# SH05-DDS.net
KiCad netlist of a schematic drawn in Altium Designer
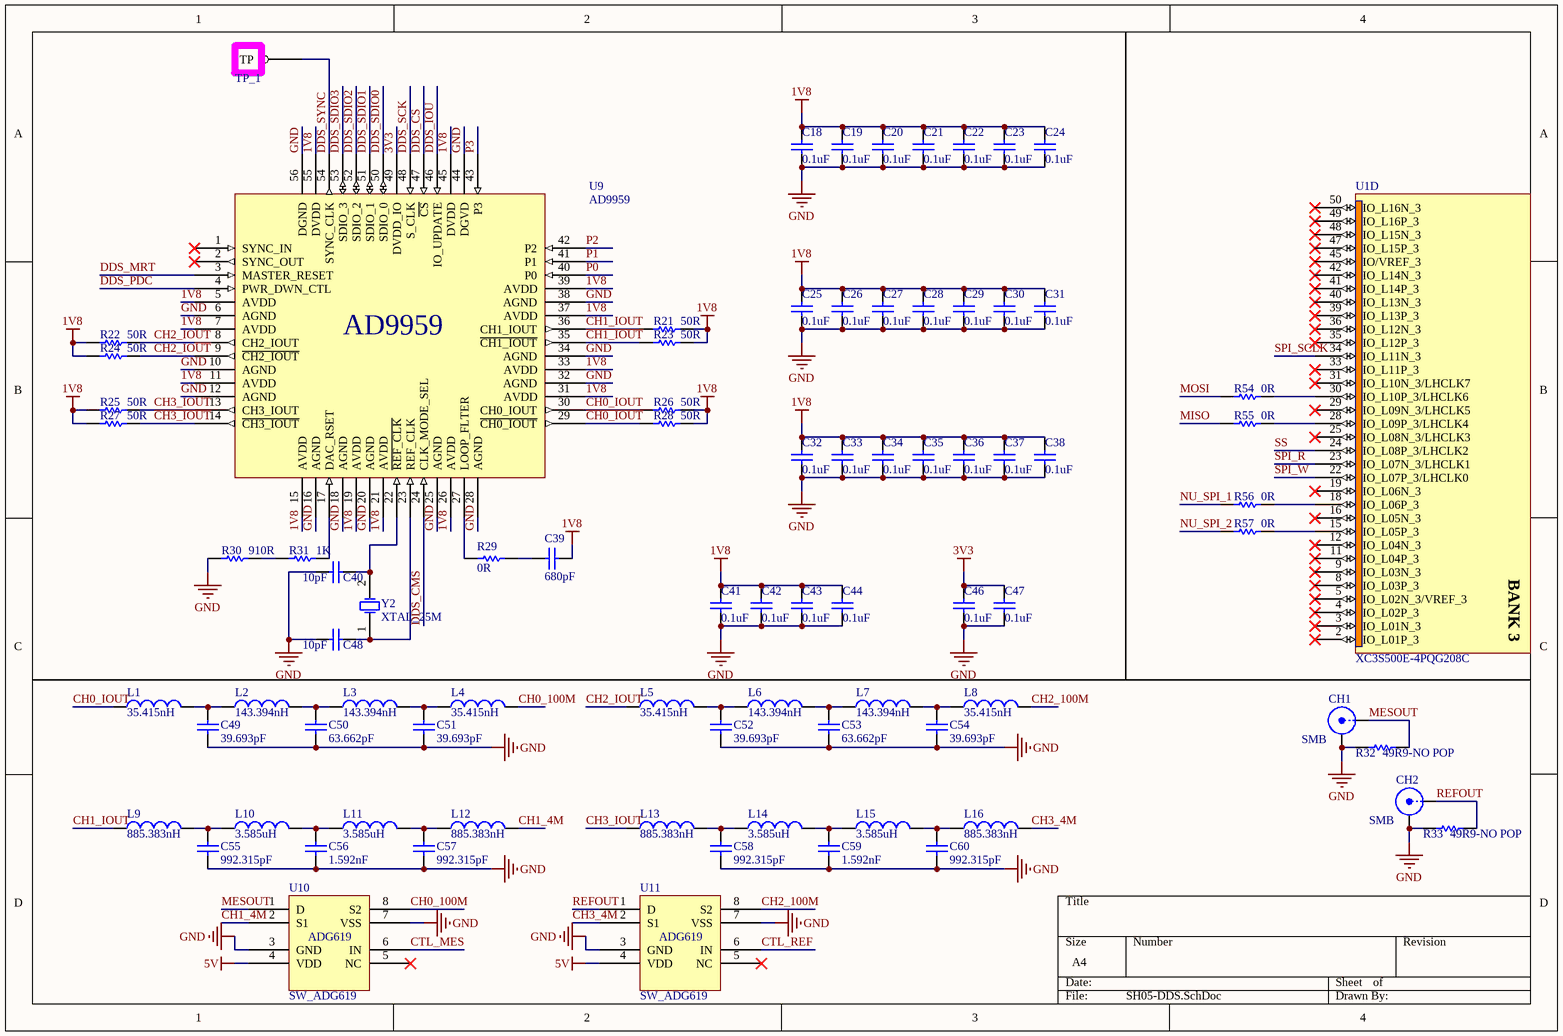
[diagram p0: SH05-DDS.SchDoc]

(export (version "E")
  (design (tool "Eeschema 10.0.6"))
  (components
    (comp (ref "C18")
      (value "0.1uF")
      (footprint "1608[0603] - NoTopOverlay")
      (description "Capacitor")
      (fields (field (name "Comment") "Cap,0.1uF/0603") (field (name "PUBLISHER") "Altium Limited"))
      (libsource (lib "Miscellaneous Devices") (part "Cap"))
    )
    (comp (ref "C19")
      (value "0.1uF")
      (footprint "1608[0603] - NoTopOverlay")
      (description "Capacitor")
      (fields (field (name "Comment") "Cap,0.1uF/0603") (field (name "PUBLISHER") "Altium Limited"))
      (libsource (lib "Miscellaneous Devices") (part "Cap"))
    )
    (comp (ref "C20")
      (value "0.1uF")
      (footprint "1608[0603] - NoTopOverlay")
      (description "Capacitor")
      (fields (field (name "Comment") "Cap,0.1uF/0603") (field (name "PUBLISHER") "Altium Limited"))
      (libsource (lib "Miscellaneous Devices") (part "Cap"))
    )
    (comp (ref "C21")
      (value "0.1uF")
      (footprint "1608[0603] - NoTopOverlay")
      (description "Capacitor")
      (fields (field (name "Comment") "Cap,0.1uF/0603") (field (name "PUBLISHER") "Altium Limited"))
      (libsource (lib "Miscellaneous Devices") (part "Cap"))
    )
    (comp (ref "C22")
      (value "0.1uF")
      (footprint "1608[0603] - NoTopOverlay")
      (description "Capacitor")
      (fields (field (name "Comment") "Cap,0.1uF/0603") (field (name "PUBLISHER") "Altium Limited"))
      (libsource (lib "Miscellaneous Devices") (part "Cap"))
    )
    (comp (ref "C23")
      (value "0.1uF")
      (footprint "1608[0603] - NoTopOverlay")
      (description "Capacitor")
      (fields (field (name "Comment") "Cap,0.1uF/0603") (field (name "PUBLISHER") "Altium Limited"))
      (libsource (lib "Miscellaneous Devices") (part "Cap"))
    )
    (comp (ref "C24")
      (value "0.1uF")
      (footprint "1608[0603] - NoTopOverlay")
      (description "Capacitor")
      (fields (field (name "Comment") "Cap,0.1uF/0603") (field (name "PUBLISHER") "Altium Limited"))
      (libsource (lib "Miscellaneous Devices") (part "Cap"))
    )
    (comp (ref "C25")
      (value "0.1uF")
      (footprint "1608[0603] - NoTopOverlay")
      (description "Capacitor")
      (fields (field (name "Comment") "Cap,0.1uF/0603") (field (name "PUBLISHER") "Altium Limited"))
      (libsource (lib "Miscellaneous Devices") (part "Cap"))
    )
    (comp (ref "C26")
      (value "0.1uF")
      (footprint "1608[0603] - NoTopOverlay")
      (description "Capacitor")
      (fields (field (name "Comment") "Cap,0.1uF/0603") (field (name "PUBLISHER") "Altium Limited"))
      (libsource (lib "Miscellaneous Devices") (part "Cap"))
    )
    (comp (ref "C27")
      (value "0.1uF")
      (footprint "1608[0603] - NoTopOverlay")
      (description "Capacitor")
      (fields (field (name "Comment") "Cap,0.1uF/0603") (field (name "PUBLISHER") "Altium Limited"))
      (libsource (lib "Miscellaneous Devices") (part "Cap"))
    )
    (comp (ref "C28")
      (value "0.1uF")
      (footprint "1608[0603] - NoTopOverlay")
      (description "Capacitor")
      (fields (field (name "Comment") "Cap,0.1uF/0603") (field (name "PUBLISHER") "Altium Limited"))
      (libsource (lib "Miscellaneous Devices") (part "Cap"))
    )
    (comp (ref "C29")
      (value "0.1uF")
      (footprint "1608[0603] - NoTopOverlay")
      (description "Capacitor")
      (fields (field (name "Comment") "Cap,0.1uF/0603") (field (name "PUBLISHER") "Altium Limited"))
      (libsource (lib "Miscellaneous Devices") (part "Cap"))
    )
    (comp (ref "C30")
      (value "0.1uF")
      (footprint "1608[0603] - NoTopOverlay")
      (description "Capacitor")
      (fields (field (name "Comment") "Cap,0.1uF/0603") (field (name "PUBLISHER") "Altium Limited"))
      (libsource (lib "Miscellaneous Devices") (part "Cap"))
    )
    (comp (ref "C31")
      (value "0.1uF")
      (footprint "1608[0603] - NoTopOverlay")
      (description "Capacitor")
      (fields (field (name "Comment") "Cap,0.1uF/0603") (field (name "PUBLISHER") "Altium Limited"))
      (libsource (lib "Miscellaneous Devices") (part "Cap"))
    )
    (comp (ref "C32")
      (value "0.1uF")
      (footprint "1608[0603] - NoTopOverlay")
      (description "Capacitor")
      (fields (field (name "Comment") "Cap,0.1uF/0603") (field (name "PUBLISHER") "Altium Limited"))
      (libsource (lib "Miscellaneous Devices") (part "Cap"))
    )
    (comp (ref "C33")
      (value "0.1uF")
      (footprint "1608[0603] - NoTopOverlay")
      (description "Capacitor")
      (fields (field (name "Comment") "Cap,0.1uF/0603") (field (name "PUBLISHER") "Altium Limited"))
      (libsource (lib "Miscellaneous Devices") (part "Cap"))
    )
    (comp (ref "C34")
      (value "0.1uF")
      (footprint "1608[0603] - NoTopOverlay")
      (description "Capacitor")
      (fields (field (name "Comment") "Cap,0.1uF/0603") (field (name "PUBLISHER") "Altium Limited"))
      (libsource (lib "Miscellaneous Devices") (part "Cap"))
    )
    (comp (ref "C35")
      (value "0.1uF")
      (footprint "1608[0603] - NoTopOverlay")
      (description "Capacitor")
      (fields (field (name "Comment") "Cap,0.1uF/0603") (field (name "PUBLISHER") "Altium Limited"))
      (libsource (lib "Miscellaneous Devices") (part "Cap"))
    )
    (comp (ref "C36")
      (value "0.1uF")
      (footprint "1608[0603] - NoTopOverlay")
      (description "Capacitor")
      (fields (field (name "Comment") "Cap,0.1uF/0603") (field (name "PUBLISHER") "Altium Limited"))
      (libsource (lib "Miscellaneous Devices") (part "Cap"))
    )
    (comp (ref "C37")
      (value "0.1uF")
      (footprint "1608[0603] - NoTopOverlay")
      (description "Capacitor")
      (fields (field (name "Comment") "Cap,0.1uF/0603") (field (name "PUBLISHER") "Altium Limited"))
      (libsource (lib "Miscellaneous Devices") (part "Cap"))
    )
    (comp (ref "C38")
      (value "0.1uF")
      (footprint "1608[0603] - NoTopOverlay")
      (description "Capacitor")
      (fields (field (name "Comment") "Cap,0.1uF/0603") (field (name "PUBLISHER") "Altium Limited"))
      (libsource (lib "Miscellaneous Devices") (part "Cap"))
    )
    (comp (ref "C39")
      (value "680pF")
      (footprint "1608[0603] - NoTopOverlay")
      (description "Capacitor")
      (fields (field (name "Comment") "Cap,680pF/0603") (field (name "PUBLISHER") "Altium Limited"))
      (libsource (lib "Miscellaneous Devices") (part "Cap"))
    )
    (comp (ref "C40")
      (value "10pF")
      (footprint "1608[0603] - NoTopOverlay")
      (description "Capacitor")
      (fields (field (name "Comment") "Cap,10pF/0603") (field (name "PUBLISHER") "Altium Limited"))
      (libsource (lib "Miscellaneous Devices") (part "Cap"))
    )
    (comp (ref "C41")
      (value "0.1uF")
      (footprint "1608[0603] - NoTopOverlay")
      (description "Capacitor")
      (fields (field (name "Comment") "Cap,0.1uF/0603") (field (name "PUBLISHER") "Altium Limited"))
      (libsource (lib "Miscellaneous Devices") (part "Cap"))
    )
    (comp (ref "C42")
      (value "0.1uF")
      (footprint "1608[0603] - NoTopOverlay")
      (description "Capacitor")
      (fields (field (name "Comment") "Cap,0.1uF/0603") (field (name "PUBLISHER") "Altium Limited"))
      (libsource (lib "Miscellaneous Devices") (part "Cap"))
    )
    (comp (ref "C43")
      (value "0.1uF")
      (footprint "1608[0603] - NoTopOverlay")
      (description "Capacitor")
      (fields (field (name "Comment") "Cap,0.1uF/0603") (field (name "PUBLISHER") "Altium Limited"))
      (libsource (lib "Miscellaneous Devices") (part "Cap"))
    )
    (comp (ref "C44")
      (value "0.1uF")
      (footprint "1608[0603] - NoTopOverlay")
      (description "Capacitor")
      (fields (field (name "Comment") "Cap,0.1uF/0603") (field (name "PUBLISHER") "Altium Limited"))
      (libsource (lib "Miscellaneous Devices") (part "Cap"))
    )
    (comp (ref "C46")
      (value "0.1uF")
      (footprint "1608[0603] - NoTopOverlay")
      (description "Capacitor")
      (fields (field (name "Comment") "Cap,0.1uF/0603") (field (name "PUBLISHER") "Altium Limited"))
      (libsource (lib "Miscellaneous Devices") (part "Cap"))
    )
    (comp (ref "C47")
      (value "0.1uF")
      (footprint "1608[0603] - NoTopOverlay")
      (description "Capacitor")
      (fields (field (name "Comment") "Cap,0.1uF/0603") (field (name "PUBLISHER") "Altium Limited"))
      (libsource (lib "Miscellaneous Devices") (part "Cap"))
    )
    (comp (ref "C48")
      (value "10pF")
      (footprint "1608[0603] - NoTopOverlay")
      (description "Capacitor")
      (fields (field (name "Comment") "Cap,10pF/0603") (field (name "PUBLISHER") "Altium Limited"))
      (libsource (lib "Miscellaneous Devices") (part "Cap"))
    )
    (comp (ref "C49")
      (value "39.693pF")
      (footprint "1608[0603] - NoTopOverlay")
      (description "Capacitor")
      (fields (field (name "Comment") "Cap,39.693pF/0603") (field (name "PUBLISHER") "Altium Limited"))
      (libsource (lib "Miscellaneous Devices") (part "Cap"))
    )
    (comp (ref "C50")
      (value "63.662pF")
      (footprint "1608[0603] - NoTopOverlay")
      (description "Capacitor")
      (fields (field (name "Comment") "Cap,63.662pF/0603") (field (name "PUBLISHER") "Altium Limited"))
      (libsource (lib "Miscellaneous Devices") (part "Cap"))
    )
    (comp (ref "C51")
      (value "39.693pF")
      (footprint "1608[0603] - NoTopOverlay")
      (description "Capacitor")
      (fields (field (name "Comment") "Cap,39.693pF/0603") (field (name "PUBLISHER") "Altium Limited"))
      (libsource (lib "Miscellaneous Devices") (part "Cap"))
    )
    (comp (ref "C52")
      (value "39.693pF")
      (footprint "1608[0603] - NoTopOverlay")
      (description "Capacitor")
      (fields (field (name "Comment") "Cap,39.693pF/0603") (field (name "PUBLISHER") "Altium Limited"))
      (libsource (lib "Miscellaneous Devices") (part "Cap"))
    )
    (comp (ref "C53")
      (value "63.662pF")
      (footprint "1608[0603] - NoTopOverlay")
      (description "Capacitor")
      (fields (field (name "Comment") "Cap,63.662pF/0603") (field (name "PUBLISHER") "Altium Limited"))
      (libsource (lib "Miscellaneous Devices") (part "Cap"))
    )
    (comp (ref "C54")
      (value "39.693pF")
      (footprint "1608[0603] - NoTopOverlay")
      (description "Capacitor")
      (fields (field (name "Comment") "Cap,39.693pF/0603") (field (name "PUBLISHER") "Altium Limited"))
      (libsource (lib "Miscellaneous Devices") (part "Cap"))
    )
    (comp (ref "C55")
      (value "992.315pF")
      (footprint "1608[0603] - NoTopOverlay")
      (description "Capacitor")
      (fields (field (name "Comment") "Cap,992.315pF/0603") (field (name "PUBLISHER") "Altium Limited"))
      (libsource (lib "Miscellaneous Devices") (part "Cap"))
    )
    (comp (ref "C56")
      (value "1.592nF")
      (footprint "1608[0603] - NoTopOverlay")
      (description "Capacitor")
      (fields (field (name "Comment") "Cap,1.592nF/0603") (field (name "PUBLISHER") "Altium Limited"))
      (libsource (lib "Miscellaneous Devices") (part "Cap"))
    )
    (comp (ref "C57")
      (value "992.315pF")
      (footprint "1608[0603] - NoTopOverlay")
      (description "Capacitor")
      (fields (field (name "Comment") "Cap,992.315pF/0603") (field (name "PUBLISHER") "Altium Limited"))
      (libsource (lib "Miscellaneous Devices") (part "Cap"))
    )
    (comp (ref "C58")
      (value "992.315pF")
      (footprint "1608[0603] - NoTopOverlay")
      (description "Capacitor")
      (fields (field (name "Comment") "Cap,992.315pF/0603") (field (name "PUBLISHER") "Altium Limited"))
      (libsource (lib "Miscellaneous Devices") (part "Cap"))
    )
    (comp (ref "C59")
      (value "1.592nF")
      (footprint "1608[0603] - NoTopOverlay")
      (description "Capacitor")
      (fields (field (name "Comment") "Cap,1.592nF/0603") (field (name "PUBLISHER") "Altium Limited"))
      (libsource (lib "Miscellaneous Devices") (part "Cap"))
    )
    (comp (ref "C60")
      (value "992.315pF")
      (footprint "1608[0603] - NoTopOverlay")
      (description "Capacitor")
      (fields (field (name "Comment") "Cap,992.315pF/0603") (field (name "PUBLISHER") "Altium Limited"))
      (libsource (lib "Miscellaneous Devices") (part "Cap"))
    )
    (comp (ref "CH1")
      (value "SMB")
      (footprint "SMB_V-RJ45")
      (description "SMB Straight Connector")
      (fields (field (name "PUBLISHER") "Altium Limited"))
      (libsource (lib "Miscellaneous Connectors") (part "SMB"))
    )
    (comp (ref "CH2")
      (value "SMB")
      (footprint "SMB_V-RJ45")
      (description "SMB Straight Connector")
      (fields (field (name "PUBLISHER") "Altium Limited"))
      (libsource (lib "Miscellaneous Connectors") (part "SMB"))
    )
    (comp (ref "L1")
      (value "35.415nH")
      (footprint "2012[0805] - NoTopOverlay")
      (description "Inductor")
      (fields (field (name "Comment") "Inductor,L0805,35.415nH") (field (name "PUBLISHER") "Altium Limited"))
      (libsource (lib "Miscellaneous Devices") (part "Inductor"))
    )
    (comp (ref "L2")
      (value "143.394nH")
      (footprint "2012[0805] - NoTopOverlay")
      (description "Inductor")
      (fields (field (name "Comment") "Inductor,L0805,143.394nH") (field (name "PUBLISHER") "Altium Limited"))
      (libsource (lib "Miscellaneous Devices") (part "Inductor"))
    )
    (comp (ref "L3")
      (value "143.394nH")
      (footprint "2012[0805] - NoTopOverlay")
      (description "Inductor")
      (fields (field (name "Comment") "Inductor,L0805,143.394nH") (field (name "PUBLISHER") "Altium Limited"))
      (libsource (lib "Miscellaneous Devices") (part "Inductor"))
    )
    (comp (ref "L4")
      (value "35.415nH")
      (footprint "2012[0805] - NoTopOverlay")
      (description "Inductor")
      (fields (field (name "Comment") "Inductor,L0805,35.415nH") (field (name "PUBLISHER") "Altium Limited"))
      (libsource (lib "Miscellaneous Devices") (part "Inductor"))
    )
    (comp (ref "L5")
      (value "35.415nH")
      (footprint "2012[0805] - NoTopOverlay")
      (description "Inductor")
      (fields (field (name "Comment") "Inductor,L0805,35.415nH") (field (name "PUBLISHER") "Altium Limited"))
      (libsource (lib "Miscellaneous Devices") (part "Inductor"))
    )
    (comp (ref "L6")
      (value "143.394nH")
      (footprint "2012[0805] - NoTopOverlay")
      (description "Inductor")
      (fields (field (name "Comment") "Inductor,L0805,143.394nH") (field (name "PUBLISHER") "Altium Limited"))
      (libsource (lib "Miscellaneous Devices") (part "Inductor"))
    )
    (comp (ref "L7")
      (value "143.394nH")
      (footprint "2012[0805] - NoTopOverlay")
      (description "Inductor")
      (fields (field (name "Comment") "Inductor,L0805,143.394nH") (field (name "PUBLISHER") "Altium Limited"))
      (libsource (lib "Miscellaneous Devices") (part "Inductor"))
    )
    (comp (ref "L8")
      (value "35.415nH")
      (footprint "2012[0805] - NoTopOverlay")
      (description "Inductor")
      (fields (field (name "Comment") "Inductor,L0805,35.415nH") (field (name "PUBLISHER") "Altium Limited"))
      (libsource (lib "Miscellaneous Devices") (part "Inductor"))
    )
    (comp (ref "L9")
      (value "885.383nH")
      (footprint "2012[0805] - NoTopOverlay")
      (description "Inductor")
      (fields (field (name "Comment") "Inductor,L0805,885.383nH") (field (name "PUBLISHER") "Altium Limited"))
      (libsource (lib "Miscellaneous Devices") (part "Inductor"))
    )
    (comp (ref "L10")
      (value "3.585uH")
      (footprint "2012[0805] - NoTopOverlay")
      (description "Inductor")
      (fields (field (name "Comment") "Inductor,L0805,3.585uH") (field (name "PUBLISHER") "Altium Limited"))
      (libsource (lib "Miscellaneous Devices") (part "Inductor"))
    )
    (comp (ref "L11")
      (value "3.585uH")
      (footprint "2012[0805] - NoTopOverlay")
      (description "Inductor")
      (fields (field (name "Comment") "Inductor,L0805,3.585uH") (field (name "PUBLISHER") "Altium Limited"))
      (libsource (lib "Miscellaneous Devices") (part "Inductor"))
    )
    (comp (ref "L12")
      (value "885.383nH")
      (footprint "2012[0805] - NoTopOverlay")
      (description "Inductor")
      (fields (field (name "Comment") "Inductor,L0805,885.383nH") (field (name "PUBLISHER") "Altium Limited"))
      (libsource (lib "Miscellaneous Devices") (part "Inductor"))
    )
    (comp (ref "L13")
      (value "885.383nH")
      (footprint "2012[0805] - NoTopOverlay")
      (description "Inductor")
      (fields (field (name "Comment") "Inductor,L0805,885.383nH") (field (name "PUBLISHER") "Altium Limited"))
      (libsource (lib "Miscellaneous Devices") (part "Inductor"))
    )
    (comp (ref "L14")
      (value "3.585uH")
      (footprint "2012[0805] - NoTopOverlay")
      (description "Inductor")
      (fields (field (name "Comment") "Inductor,L0805,3.585uH") (field (name "PUBLISHER") "Altium Limited"))
      (libsource (lib "Miscellaneous Devices") (part "Inductor"))
    )
    (comp (ref "L15")
      (value "3.585uH")
      (footprint "2012[0805] - NoTopOverlay")
      (description "Inductor")
      (fields (field (name "Comment") "Inductor,L0805,3.585uH") (field (name "PUBLISHER") "Altium Limited"))
      (libsource (lib "Miscellaneous Devices") (part "Inductor"))
    )
    (comp (ref "L16")
      (value "885.383nH")
      (footprint "2012[0805] - NoTopOverlay")
      (description "Inductor")
      (fields (field (name "Comment") "Inductor,L0805,885.383nH") (field (name "PUBLISHER") "Altium Limited"))
      (libsource (lib "Miscellaneous Devices") (part "Inductor"))
    )
    (comp (ref "R21")
      (value "50R")
      (footprint "1608[0603] - NoTopOverlay")
      (description "Resistor")
      (fields (field (name "Comment") "Res,50R/0603") (field (name "PUBLISHER") "Altium Limited"))
      (libsource (lib "Miscellaneous Devices") (part "Res1"))
    )
    (comp (ref "R22")
      (value "50R")
      (footprint "1608[0603] - NoTopOverlay")
      (description "Resistor")
      (fields (field (name "Comment") "Res,50R/0603") (field (name "PUBLISHER") "Altium Limited"))
      (libsource (lib "Miscellaneous Devices") (part "Res1"))
    )
    (comp (ref "R23")
      (value "50R")
      (footprint "1608[0603] - NoTopOverlay")
      (description "Resistor")
      (fields (field (name "Comment") "Res,50R/0603") (field (name "PUBLISHER") "Altium Limited"))
      (libsource (lib "Miscellaneous Devices") (part "Res1"))
    )
    (comp (ref "R24")
      (value "50R")
      (footprint "1608[0603] - NoTopOverlay")
      (description "Resistor")
      (fields (field (name "Comment") "Res,50R/0603") (field (name "PUBLISHER") "Altium Limited"))
      (libsource (lib "Miscellaneous Devices") (part "Res1"))
    )
    (comp (ref "R25")
      (value "50R")
      (footprint "1608[0603] - NoTopOverlay")
      (description "Resistor")
      (fields (field (name "Comment") "Res,50R/0603") (field (name "PUBLISHER") "Altium Limited"))
      (libsource (lib "Miscellaneous Devices") (part "Res1"))
    )
    (comp (ref "R26")
      (value "50R")
      (footprint "1608[0603] - NoTopOverlay")
      (description "Resistor")
      (fields (field (name "Comment") "Res,50R/0603") (field (name "PUBLISHER") "Altium Limited"))
      (libsource (lib "Miscellaneous Devices") (part "Res1"))
    )
    (comp (ref "R27")
      (value "50R")
      (footprint "1608[0603] - NoTopOverlay")
      (description "Resistor")
      (fields (field (name "Comment") "Res,50R/0603") (field (name "PUBLISHER") "Altium Limited"))
      (libsource (lib "Miscellaneous Devices") (part "Res1"))
    )
    (comp (ref "R28")
      (value "50R")
      (footprint "1608[0603] - NoTopOverlay")
      (description "Resistor")
      (fields (field (name "Comment") "Res,50R/0603") (field (name "PUBLISHER") "Altium Limited"))
      (libsource (lib "Miscellaneous Devices") (part "Res1"))
    )
    (comp (ref "R29")
      (value "0R")
      (footprint "1608[0603] - NoTopOverlay")
      (description "Resistor")
      (fields (field (name "Comment") "Res,0R/0603") (field (name "PUBLISHER") "Altium Limited"))
      (libsource (lib "Miscellaneous Devices") (part "Res1"))
    )
    (comp (ref "R30")
      (value "910R")
      (footprint "1608[0603] - NoTopOverlay")
      (description "Resistor")
      (fields (field (name "Comment") "Res,910R/0603") (field (name "PUBLISHER") "Altium Limited"))
      (libsource (lib "Miscellaneous Devices") (part "Res1"))
    )
    (comp (ref "R31")
      (value "1K")
      (footprint "1608[0603] - NoTopOverlay")
      (description "Resistor")
      (fields (field (name "Comment") "Res,1K/0805") (field (name "PUBLISHER") "Altium Limited"))
      (libsource (lib "Miscellaneous Devices") (part "Res1"))
    )
    (comp (ref "R32")
      (value "49R9-NO POP")
      (footprint "1608[0603] - NoTopOverlay")
      (description "Resistor")
      (fields (field (name "Comment") "Res,49R9/0603") (field (name "PUBLISHER") "Altium Limited"))
      (libsource (lib "Miscellaneous Devices") (part "Res1"))
    )
    (comp (ref "R33")
      (value "49R9-NO POP")
      (footprint "1608[0603] - NoTopOverlay")
      (description "Resistor")
      (fields (field (name "Comment") "Res,49R9/0603") (field (name "PUBLISHER") "Altium Limited"))
      (libsource (lib "Miscellaneous Devices") (part "Res1"))
    )
    (comp (ref "R54")
      (value "0R")
      (footprint "1608[0603] - NoTopOverlay")
      (description "Resistor")
      (fields (field (name "Comment") "Res,0R/0603") (field (name "PUBLISHER") "Altium Limited"))
      (libsource (lib "Miscellaneous Devices") (part "Res1"))
    )
    (comp (ref "R55")
      (value "0R")
      (footprint "1608[0603] - NoTopOverlay")
      (description "Resistor")
      (fields (field (name "Comment") "Res,0R/0603") (field (name "PUBLISHER") "Altium Limited"))
      (libsource (lib "Miscellaneous Devices") (part "Res1"))
    )
    (comp (ref "R56")
      (value "0R")
      (footprint "1608[0603] - NoTopOverlay")
      (description "Resistor")
      (fields (field (name "Comment") "Res,0R/0603") (field (name "PUBLISHER") "Altium Limited"))
      (libsource (lib "Miscellaneous Devices") (part "Res1"))
    )
    (comp (ref "R57")
      (value "0R")
      (footprint "1608[0603] - NoTopOverlay")
      (description "Resistor")
      (fields (field (name "Comment") "Res,0R/0603") (field (name "PUBLISHER") "Altium Limited"))
      (libsource (lib "Miscellaneous Devices") (part "Res1"))
    )
    (comp (ref "TP_1")
      (value "TP_DDS_SYNC_CLK")
      (footprint "MYTP")
      (libsource (lib "*") (part "TEST POINT_0"))
    )
    (comp (ref "U1")
      (value "XC3S500E-4PQG208C")
      (footprint "PQG208_N")
      (description "Spartan-3E 1.2V FPGA, 158 User I/Os, 208-Pin Pb-Free PQFP, Standard Performance, Commercial Grade")
      (fields (field (name "PUBLISHER") "Altium Limited"))
      (libsource (lib "Xilinx Spartan-3E") (part "XC3S500E-4PQG208C"))
    )
    (comp (ref "U9")
      (value "AD9959")
      (footprint "CP-56")
      (libsource (lib "Laser-LiuXin") (part "DDS_AD9959"))
    )
    (comp (ref "U10")
      (value "SW_ADG619")
      (footprint "Laser-LiuXin:SOT23D")
      (description "Single SPDT Switches")
      (libsource (lib "Laser-LiuXin") (part "SW_ADG619"))
    )
    (comp (ref "U11")
      (value "SW_ADG619")
      (footprint "Laser-LiuXin:SOT23D")
      (description "Single SPDT Switches")
      (libsource (lib "Laser-LiuXin") (part "SW_ADG619"))
    )
    (comp (ref "Y2")
      (value "XTAL_25M")
      (footprint "DSP_communicate:XTAL2")
      (description "Crystal Oscillator")
      (fields (field (name "PUBLISHER") "Altium Limited"))
      (libsource (lib "Miscellaneous Devices") (part "XTAL"))
    )
  )
  (nets
    (net (code "1") (name "/CH0_100M") (class "Default")
      (node (ref "L4") (pin "2") (pinfunction "2_2") (pintype "passive"))
      (node (ref "U10") (pin "8") (pinfunction "S2_8") (pintype "passive"))
    )
    (net (code "2") (name "/CH0_IOUT") (class "Default")
      (node (ref "L1") (pin "1") (pinfunction "1_1") (pintype "passive"))
      (node (ref "R26") (pin "1") (pinfunction "1_1") (pintype "passive"))
      (node (ref "U9") (pin "30") (pinfunction "CH0_IOUT_30") (pintype "output"))
    )
    (net (code "3") (name "/CH1_4M") (class "Default")
      (node (ref "L12") (pin "2") (pinfunction "2_2") (pintype "passive"))
      (node (ref "U10") (pin "2") (pinfunction "S1_2") (pintype "passive"))
    )
    (net (code "4") (name "/CH1_IOUT") (class "Default")
      (node (ref "L9") (pin "1") (pinfunction "1_1") (pintype "passive"))
      (node (ref "R21") (pin "1") (pinfunction "1_1") (pintype "passive"))
      (node (ref "U9") (pin "36") (pinfunction "CH1_IOUT_36") (pintype "output"))
    )
    (net (code "5") (name "/CH2_100M") (class "Default")
      (node (ref "L8") (pin "2") (pinfunction "2_2") (pintype "passive"))
      (node (ref "U11") (pin "8") (pinfunction "S2_8") (pintype "passive"))
    )
    (net (code "6") (name "/CH2_IOUT") (class "Default")
      (node (ref "L5") (pin "1") (pinfunction "1_1") (pintype "passive"))
      (node (ref "R22") (pin "2") (pinfunction "2_2") (pintype "passive"))
      (node (ref "U9") (pin "8") (pinfunction "CH2_IOUT_8") (pintype "output"))
    )
    (net (code "7") (name "/CH3_4M") (class "Default")
      (node (ref "L16") (pin "2") (pinfunction "2_2") (pintype "passive"))
      (node (ref "U11") (pin "2") (pinfunction "S1_2") (pintype "passive"))
    )
    (net (code "8") (name "/CH3_IOUT") (class "Default")
      (node (ref "L13") (pin "1") (pinfunction "1_1") (pintype "passive"))
      (node (ref "R25") (pin "2") (pinfunction "2_2") (pintype "passive"))
      (node (ref "U9") (pin "13") (pinfunction "CH3_IOUT_13") (pintype "output"))
    )
    (net (code "9") (name "/CTL_MES") (class "Default")
      (node (ref "U10") (pin "6") (pinfunction "IN_6") (pintype "passive"))
    )
    (net (code "10") (name "/CTL_REF") (class "Default")
      (node (ref "U11") (pin "6") (pinfunction "IN_6") (pintype "passive"))
    )
    (net (code "11") (name "/DDS_CMS") (class "Default")
      (node (ref "U9") (pin "24") (pinfunction "CLK_MODE_SEL_24") (pintype "input"))
    )
    (net (code "12") (name "/DDS_IOU") (class "Default")
      (node (ref "U9") (pin "46") (pinfunction "IO_UPDATE_46") (pintype "input"))
    )
    (net (code "13") (name "/DDS_MRT") (class "Default")
      (node (ref "U9") (pin "3") (pinfunction "MASTER_RESET_3") (pintype "input"))
    )
    (net (code "14") (name "/DDS_PDC") (class "Default")
      (node (ref "U9") (pin "4") (pinfunction "PWR_DWN_CTL_4") (pintype "input"))
    )
    (net (code "15") (name "/DDS_SCK") (class "Default")
      (node (ref "U9") (pin "48") (pinfunction "S_CLK_48") (pintype "input"))
    )
    (net (code "16") (name "/DDS_SDIO0") (class "Default")
      (node (ref "U9") (pin "50") (pinfunction "SDIO_0_50") (pintype "bidirectional"))
    )
    (net (code "17") (name "/DDS_SDIO1") (class "Default")
      (node (ref "U9") (pin "51") (pinfunction "SDIO_1_51") (pintype "bidirectional"))
    )
    (net (code "18") (name "/DDS_SDIO2") (class "Default")
      (node (ref "U9") (pin "52") (pinfunction "SDIO_2_52") (pintype "bidirectional"))
    )
    (net (code "19") (name "/DDS_SDIO3") (class "Default")
      (node (ref "U9") (pin "53") (pinfunction "SDIO_3_53") (pintype "bidirectional"))
    )
    (net (code "20") (name "/DDS_SYNC") (class "Default")
      (node (ref "TP_1") (pin "1") (pinfunction "TP_1") (pintype "passive"))
      (node (ref "U9") (pin "54") (pinfunction "SYNC_CLK_54") (pintype "output"))
    )
    (net (code "21") (name "/DDS~{_CS}") (class "Default")
      (node (ref "U9") (pin "47") (pinfunction "~{CS}_47") (pintype "input"))
    )
    (net (code "22") (name "/MESOUT") (class "Default")
      (node (ref "CH1") (pin "1") (pinfunction "X_1") (pintype "passive"))
      (node (ref "R32") (pin "1") (pinfunction "1_1") (pintype "passive"))
      (node (ref "U10") (pin "1") (pinfunction "D_1") (pintype "passive"))
    )
    (net (code "23") (name "/MISO") (class "Default")
      (node (ref "R55") (pin "2") (pinfunction "2_2") (pintype "passive"))
    )
    (net (code "24") (name "/MOSI") (class "Default")
      (node (ref "R54") (pin "2") (pinfunction "2_2") (pintype "passive"))
    )
    (net (code "25") (name "/NU_SPI_1") (class "Default")
      (node (ref "R56") (pin "2") (pinfunction "2_2") (pintype "passive"))
    )
    (net (code "26") (name "/NU_SPI_2") (class "Default")
      (node (ref "R57") (pin "2") (pinfunction "2_2") (pintype "passive"))
    )
    (net (code "27") (name "/P0") (class "Default")
      (node (ref "U9") (pin "40") (pinfunction "P0_40") (pintype "input"))
    )
    (net (code "28") (name "/P1") (class "Default")
      (node (ref "U9") (pin "41") (pinfunction "P1_41") (pintype "input"))
    )
    (net (code "29") (name "/P2") (class "Default")
      (node (ref "U9") (pin "42") (pinfunction "P2_42") (pintype "input"))
    )
    (net (code "30") (name "/P3") (class "Default")
      (node (ref "U9") (pin "43") (pinfunction "P3_43") (pintype "input"))
    )
    (net (code "31") (name "/REFOUT") (class "Default")
      (node (ref "CH2") (pin "1") (pinfunction "X_1") (pintype "passive"))
      (node (ref "R33") (pin "1") (pinfunction "1_1") (pintype "passive"))
      (node (ref "U11") (pin "1") (pinfunction "D_1") (pintype "passive"))
    )
    (net (code "32") (name "/SPI_R") (class "Default")
      (node (ref "U1") (pin "23") (pinfunction "IO_L07N_3/LHCLK1_23") (pintype "bidirectional"))
    )
    (net (code "33") (name "/SPI_SCLK") (class "Default")
      (node (ref "U1") (pin "34") (pinfunction "IO_L11N_3_34") (pintype "bidirectional"))
    )
    (net (code "34") (name "/SPI_W") (class "Default")
      (node (ref "U1") (pin "22") (pinfunction "IO_L07P_3/LHCLK0_22") (pintype "bidirectional"))
    )
    (net (code "35") (name "/SS") (class "Default")
      (node (ref "U1") (pin "24") (pinfunction "IO_L08P_3/LHCLK2_24") (pintype "bidirectional"))
    )
    (net (code "36") (name "/~{CH0_IOUT}") (class "Default")
      (node (ref "R28") (pin "1") (pinfunction "1_1") (pintype "passive"))
      (node (ref "U9") (pin "29") (pinfunction "~{CH0_IOUT}_29") (pintype "output"))
    )
    (net (code "37") (name "/~{CH1_IOUT}") (class "Default")
      (node (ref "R23") (pin "1") (pinfunction "1_1") (pintype "passive"))
      (node (ref "U9") (pin "35") (pinfunction "~{CH1_IOUT}_35") (pintype "output"))
    )
    (net (code "38") (name "/~{CH2_IOUT}") (class "Default")
      (node (ref "R24") (pin "2") (pinfunction "2_2") (pintype "passive"))
      (node (ref "U9") (pin "9") (pinfunction "~{CH2_IOUT}_9") (pintype "output"))
    )
    (net (code "39") (name "/~{CH3_IOUT}") (class "Default")
      (node (ref "R27") (pin "2") (pinfunction "2_2") (pintype "passive"))
      (node (ref "U9") (pin "14") (pinfunction "~{CH3_IOUT}_14") (pintype "output"))
    )
    (net (code "40") (name "1V8") (class "Default")
      (node (ref "C18") (pin "1") (pinfunction "1_1") (pintype "passive"))
      (node (ref "C19") (pin "1") (pinfunction "1_1") (pintype "passive"))
      (node (ref "C20") (pin "1") (pinfunction "1_1") (pintype "passive"))
      (node (ref "C21") (pin "1") (pinfunction "1_1") (pintype "passive"))
      (node (ref "C22") (pin "1") (pinfunction "1_1") (pintype "passive"))
      (node (ref "C23") (pin "1") (pinfunction "1_1") (pintype "passive"))
      (node (ref "C24") (pin "1") (pinfunction "1_1") (pintype "passive"))
      (node (ref "C25") (pin "1") (pinfunction "1_1") (pintype "passive"))
      (node (ref "C26") (pin "1") (pinfunction "1_1") (pintype "passive"))
      (node (ref "C27") (pin "1") (pinfunction "1_1") (pintype "passive"))
      (node (ref "C28") (pin "1") (pinfunction "1_1") (pintype "passive"))
      (node (ref "C29") (pin "1") (pinfunction "1_1") (pintype "passive"))
      (node (ref "C30") (pin "1") (pinfunction "1_1") (pintype "passive"))
      (node (ref "C31") (pin "1") (pinfunction "1_1") (pintype "passive"))
      (node (ref "C32") (pin "1") (pinfunction "1_1") (pintype "passive"))
      (node (ref "C33") (pin "1") (pinfunction "1_1") (pintype "passive"))
      (node (ref "C34") (pin "1") (pinfunction "1_1") (pintype "passive"))
      (node (ref "C35") (pin "1") (pinfunction "1_1") (pintype "passive"))
      (node (ref "C36") (pin "1") (pinfunction "1_1") (pintype "passive"))
      (node (ref "C37") (pin "1") (pinfunction "1_1") (pintype "passive"))
      (node (ref "C38") (pin "1") (pinfunction "1_1") (pintype "passive"))
      (node (ref "C39") (pin "1") (pinfunction "1_1") (pintype "passive"))
      (node (ref "C41") (pin "1") (pinfunction "1_1") (pintype "passive"))
      (node (ref "C42") (pin "1") (pinfunction "1_1") (pintype "passive"))
      (node (ref "C43") (pin "1") (pinfunction "1_1") (pintype "passive"))
      (node (ref "C44") (pin "1") (pinfunction "1_1") (pintype "passive"))
      (node (ref "R21") (pin "2") (pinfunction "2_2") (pintype "passive"))
      (node (ref "R22") (pin "1") (pinfunction "1_1") (pintype "passive"))
      (node (ref "R23") (pin "2") (pinfunction "2_2") (pintype "passive"))
      (node (ref "R24") (pin "1") (pinfunction "1_1") (pintype "passive"))
      (node (ref "R25") (pin "1") (pinfunction "1_1") (pintype "passive"))
      (node (ref "R26") (pin "2") (pinfunction "2_2") (pintype "passive"))
      (node (ref "R27") (pin "1") (pinfunction "1_1") (pintype "passive"))
      (node (ref "R28") (pin "2") (pinfunction "2_2") (pintype "passive"))
      (node (ref "U9") (pin "11") (pinfunction "AVDD_11") (pintype "power_in"))
      (node (ref "U9") (pin "15") (pinfunction "AVDD_15") (pintype "power_in"))
      (node (ref "U9") (pin "19") (pinfunction "AVDD_19") (pintype "power_in"))
      (node (ref "U9") (pin "21") (pinfunction "AVDD_21") (pintype "power_in"))
      (node (ref "U9") (pin "26") (pinfunction "AVDD_26") (pintype "power_in"))
      (node (ref "U9") (pin "31") (pinfunction "AVDD_31") (pintype "power_in"))
      (node (ref "U9") (pin "33") (pinfunction "AVDD_33") (pintype "power_in"))
      (node (ref "U9") (pin "37") (pinfunction "AVDD_37") (pintype "power_in"))
      (node (ref "U9") (pin "39") (pinfunction "AVDD_39") (pintype "power_in"))
      (node (ref "U9") (pin "45") (pinfunction "DVDD_45") (pintype "power_in"))
      (node (ref "U9") (pin "5") (pinfunction "AVDD_5") (pintype "power_in"))
      (node (ref "U9") (pin "55") (pinfunction "DVDD_55") (pintype "power_in"))
      (node (ref "U9") (pin "7") (pinfunction "AVDD_7") (pintype "power_in"))
    )
    (net (code "41") (name "3V3") (class "Default")
      (node (ref "C46") (pin "1") (pinfunction "1_1") (pintype "passive"))
      (node (ref "C47") (pin "1") (pinfunction "1_1") (pintype "passive"))
      (node (ref "U9") (pin "49") (pinfunction "DVDD_IO_49") (pintype "power_in"))
    )
    (net (code "42") (name "5V") (class "Default")
      (node (ref "U10") (pin "4") (pinfunction "VDD_4") (pintype "passive"))
      (node (ref "U11") (pin "4") (pinfunction "VDD_4") (pintype "passive"))
    )
    (net (code "43") (name "GND") (class "Default")
      (node (ref "C18") (pin "2") (pinfunction "2_2") (pintype "passive"))
      (node (ref "C19") (pin "2") (pinfunction "2_2") (pintype "passive"))
      (node (ref "C20") (pin "2") (pinfunction "2_2") (pintype "passive"))
      (node (ref "C21") (pin "2") (pinfunction "2_2") (pintype "passive"))
      (node (ref "C22") (pin "2") (pinfunction "2_2") (pintype "passive"))
      (node (ref "C23") (pin "2") (pinfunction "2_2") (pintype "passive"))
      (node (ref "C24") (pin "2") (pinfunction "2_2") (pintype "passive"))
      (node (ref "C25") (pin "2") (pinfunction "2_2") (pintype "passive"))
      (node (ref "C26") (pin "2") (pinfunction "2_2") (pintype "passive"))
      (node (ref "C27") (pin "2") (pinfunction "2_2") (pintype "passive"))
      (node (ref "C28") (pin "2") (pinfunction "2_2") (pintype "passive"))
      (node (ref "C29") (pin "2") (pinfunction "2_2") (pintype "passive"))
      (node (ref "C30") (pin "2") (pinfunction "2_2") (pintype "passive"))
      (node (ref "C31") (pin "2") (pinfunction "2_2") (pintype "passive"))
      (node (ref "C32") (pin "2") (pinfunction "2_2") (pintype "passive"))
      (node (ref "C33") (pin "2") (pinfunction "2_2") (pintype "passive"))
      (node (ref "C34") (pin "2") (pinfunction "2_2") (pintype "passive"))
      (node (ref "C35") (pin "2") (pinfunction "2_2") (pintype "passive"))
      (node (ref "C36") (pin "2") (pinfunction "2_2") (pintype "passive"))
      (node (ref "C37") (pin "2") (pinfunction "2_2") (pintype "passive"))
      (node (ref "C38") (pin "2") (pinfunction "2_2") (pintype "passive"))
      (node (ref "C40") (pin "1") (pinfunction "1_1") (pintype "passive"))
      (node (ref "C41") (pin "2") (pinfunction "2_2") (pintype "passive"))
      (node (ref "C42") (pin "2") (pinfunction "2_2") (pintype "passive"))
      (node (ref "C43") (pin "2") (pinfunction "2_2") (pintype "passive"))
      (node (ref "C44") (pin "2") (pinfunction "2_2") (pintype "passive"))
      (node (ref "C46") (pin "2") (pinfunction "2_2") (pintype "passive"))
      (node (ref "C47") (pin "2") (pinfunction "2_2") (pintype "passive"))
      (node (ref "C48") (pin "2") (pinfunction "2_2") (pintype "passive"))
      (node (ref "C49") (pin "2") (pinfunction "2_2") (pintype "passive"))
      (node (ref "C50") (pin "2") (pinfunction "2_2") (pintype "passive"))
      (node (ref "C51") (pin "2") (pinfunction "2_2") (pintype "passive"))
      (node (ref "C52") (pin "2") (pinfunction "2_2") (pintype "passive"))
      (node (ref "C53") (pin "2") (pinfunction "2_2") (pintype "passive"))
      (node (ref "C54") (pin "2") (pinfunction "2_2") (pintype "passive"))
      (node (ref "C55") (pin "2") (pinfunction "2_2") (pintype "passive"))
      (node (ref "C56") (pin "2") (pinfunction "2_2") (pintype "passive"))
      (node (ref "C57") (pin "2") (pinfunction "2_2") (pintype "passive"))
      (node (ref "C58") (pin "2") (pinfunction "2_2") (pintype "passive"))
      (node (ref "C59") (pin "2") (pinfunction "2_2") (pintype "passive"))
      (node (ref "C60") (pin "2") (pinfunction "2_2") (pintype "passive"))
      (node (ref "CH1") (pin "2") (pinfunction "Y_2") (pintype "passive"))
      (node (ref "CH2") (pin "2") (pinfunction "Y_2") (pintype "passive"))
      (node (ref "R30") (pin "2") (pinfunction "2_2") (pintype "passive"))
      (node (ref "R32") (pin "2") (pinfunction "2_2") (pintype "passive"))
      (node (ref "R33") (pin "2") (pinfunction "2_2") (pintype "passive"))
      (node (ref "U10") (pin "3") (pinfunction "GND_3") (pintype "passive"))
      (node (ref "U10") (pin "7") (pinfunction "VSS_7") (pintype "passive"))
      (node (ref "U11") (pin "3") (pinfunction "GND_3") (pintype "passive"))
      (node (ref "U11") (pin "7") (pinfunction "VSS_7") (pintype "passive"))
      (node (ref "U9") (pin "10") (pinfunction "AGND_10") (pintype "passive"))
      (node (ref "U9") (pin "12") (pinfunction "AGND_12") (pintype "passive"))
      (node (ref "U9") (pin "16") (pinfunction "AGND_16") (pintype "passive"))
      (node (ref "U9") (pin "18") (pinfunction "AGND_18") (pintype "passive"))
      (node (ref "U9") (pin "20") (pinfunction "AGND_20") (pintype "passive"))
      (node (ref "U9") (pin "25") (pinfunction "AGND_25") (pintype "passive"))
      (node (ref "U9") (pin "28") (pinfunction "AGND_28") (pintype "passive"))
      (node (ref "U9") (pin "32") (pinfunction "AGND_32") (pintype "passive"))
      (node (ref "U9") (pin "34") (pinfunction "AGND_34") (pintype "passive"))
      (node (ref "U9") (pin "38") (pinfunction "AGND_38") (pintype "passive"))
      (node (ref "U9") (pin "44") (pinfunction "DGVD_44") (pintype "power_in"))
      (node (ref "U9") (pin "56") (pinfunction "DGND_56") (pintype "power_in"))
      (node (ref "U9") (pin "6") (pinfunction "AGND_6") (pintype "passive"))
    )
    (net (code "44") (name "Net-(C39-Pad2)") (class "Default")
      (node (ref "C39") (pin "2") (pinfunction "2_2") (pintype "passive"))
      (node (ref "R29") (pin "1") (pinfunction "1_1") (pintype "passive"))
    )
    (net (code "45") (name "Net-(C49-Pad1)") (class "Default")
      (node (ref "C49") (pin "1") (pinfunction "1_1") (pintype "passive"))
      (node (ref "L1") (pin "2") (pinfunction "2_2") (pintype "passive"))
      (node (ref "L2") (pin "1") (pinfunction "1_1") (pintype "passive"))
    )
    (net (code "46") (name "Net-(C50-Pad1)") (class "Default")
      (node (ref "C50") (pin "1") (pinfunction "1_1") (pintype "passive"))
      (node (ref "L2") (pin "2") (pinfunction "2_2") (pintype "passive"))
      (node (ref "L3") (pin "1") (pinfunction "1_1") (pintype "passive"))
    )
    (net (code "47") (name "Net-(C51-Pad1)") (class "Default")
      (node (ref "C51") (pin "1") (pinfunction "1_1") (pintype "passive"))
      (node (ref "L3") (pin "2") (pinfunction "2_2") (pintype "passive"))
      (node (ref "L4") (pin "1") (pinfunction "1_1") (pintype "passive"))
    )
    (net (code "48") (name "Net-(C52-Pad1)") (class "Default")
      (node (ref "C52") (pin "1") (pinfunction "1_1") (pintype "passive"))
      (node (ref "L5") (pin "2") (pinfunction "2_2") (pintype "passive"))
      (node (ref "L6") (pin "1") (pinfunction "1_1") (pintype "passive"))
    )
    (net (code "49") (name "Net-(C53-Pad1)") (class "Default")
      (node (ref "C53") (pin "1") (pinfunction "1_1") (pintype "passive"))
      (node (ref "L6") (pin "2") (pinfunction "2_2") (pintype "passive"))
      (node (ref "L7") (pin "1") (pinfunction "1_1") (pintype "passive"))
    )
    (net (code "50") (name "Net-(C54-Pad1)") (class "Default")
      (node (ref "C54") (pin "1") (pinfunction "1_1") (pintype "passive"))
      (node (ref "L7") (pin "2") (pinfunction "2_2") (pintype "passive"))
      (node (ref "L8") (pin "1") (pinfunction "1_1") (pintype "passive"))
    )
    (net (code "51") (name "Net-(C55-Pad1)") (class "Default")
      (node (ref "C55") (pin "1") (pinfunction "1_1") (pintype "passive"))
      (node (ref "L10") (pin "1") (pinfunction "1_1") (pintype "passive"))
      (node (ref "L9") (pin "2") (pinfunction "2_2") (pintype "passive"))
    )
    (net (code "52") (name "Net-(C56-Pad1)") (class "Default")
      (node (ref "C56") (pin "1") (pinfunction "1_1") (pintype "passive"))
      (node (ref "L10") (pin "2") (pinfunction "2_2") (pintype "passive"))
      (node (ref "L11") (pin "1") (pinfunction "1_1") (pintype "passive"))
    )
    (net (code "53") (name "Net-(C57-Pad1)") (class "Default")
      (node (ref "C57") (pin "1") (pinfunction "1_1") (pintype "passive"))
      (node (ref "L11") (pin "2") (pinfunction "2_2") (pintype "passive"))
      (node (ref "L12") (pin "1") (pinfunction "1_1") (pintype "passive"))
    )
    (net (code "54") (name "Net-(C58-Pad1)") (class "Default")
      (node (ref "C58") (pin "1") (pinfunction "1_1") (pintype "passive"))
      (node (ref "L13") (pin "2") (pinfunction "2_2") (pintype "passive"))
      (node (ref "L14") (pin "1") (pinfunction "1_1") (pintype "passive"))
    )
    (net (code "55") (name "Net-(C59-Pad1)") (class "Default")
      (node (ref "C59") (pin "1") (pinfunction "1_1") (pintype "passive"))
      (node (ref "L14") (pin "2") (pinfunction "2_2") (pintype "passive"))
      (node (ref "L15") (pin "1") (pinfunction "1_1") (pintype "passive"))
    )
    (net (code "56") (name "Net-(C60-Pad1)") (class "Default")
      (node (ref "C60") (pin "1") (pinfunction "1_1") (pintype "passive"))
      (node (ref "L15") (pin "2") (pinfunction "2_2") (pintype "passive"))
      (node (ref "L16") (pin "1") (pinfunction "1_1") (pintype "passive"))
    )
    (net (code "57") (name "Net-(R30-Pad1)") (class "Default")
      (node (ref "R30") (pin "1") (pinfunction "1_1") (pintype "passive"))
      (node (ref "R31") (pin "2") (pinfunction "2_2") (pintype "passive"))
    )
    (net (code "58") (name "Net-(U1D-IO_L05P_3)") (class "Default")
      (node (ref "R57") (pin "1") (pinfunction "1_1") (pintype "passive"))
      (node (ref "U1") (pin "15") (pinfunction "IO_L05P_3_15") (pintype "bidirectional"))
    )
    (net (code "59") (name "Net-(U1D-IO_L06P_3)") (class "Default")
      (node (ref "R56") (pin "1") (pinfunction "1_1") (pintype "passive"))
      (node (ref "U1") (pin "18") (pinfunction "IO_L06P_3_18") (pintype "bidirectional"))
    )
    (net (code "60") (name "Net-(U1D-IO_L09P_3{slash}LHCLK4)") (class "Default")
      (node (ref "R55") (pin "1") (pinfunction "1_1") (pintype "passive"))
      (node (ref "U1") (pin "28") (pinfunction "IO_L09P_3/LHCLK4_28") (pintype "bidirectional"))
    )
    (net (code "61") (name "Net-(U1D-IO_L10P_3{slash}LHCLK6)") (class "Default")
      (node (ref "R54") (pin "1") (pinfunction "1_1") (pintype "passive"))
      (node (ref "U1") (pin "30") (pinfunction "IO_L10P_3/LHCLK6_30") (pintype "bidirectional"))
    )
    (net (code "62") (name "Net-(U9-DAC_RSET)") (class "Default")
      (node (ref "R31") (pin "1") (pinfunction "1_1") (pintype "passive"))
      (node (ref "U9") (pin "17") (pinfunction "DAC_RSET_17") (pintype "input"))
    )
    (net (code "63") (name "Net-(U9-LOOP_FLTER)") (class "Default")
      (node (ref "R29") (pin "2") (pinfunction "2_2") (pintype "passive"))
      (node (ref "U9") (pin "27") (pinfunction "LOOP_FLTER_27") (pintype "passive"))
    )
    (net (code "64") (name "Net-(U9-REF_CLK)") (class "Default")
      (node (ref "C48") (pin "1") (pinfunction "1_1") (pintype "passive"))
      (node (ref "U9") (pin "23") (pinfunction "REF_CLK_23") (pintype "input"))
      (node (ref "Y2") (pin "1") (pinfunction "OSC1_1") (pintype "passive"))
    )
    (net (code "65") (name "Net-(U9-~{REF_CLK})") (class "Default")
      (node (ref "C40") (pin "2") (pinfunction "2_2") (pintype "passive"))
      (node (ref "U9") (pin "22") (pinfunction "~{REF_CLK}_22") (pintype "input"))
      (node (ref "Y2") (pin "2") (pinfunction "OSC2_2") (pintype "passive"))
    )
    (net (code "66") (name "unconnected-(U1D-IO_L01N_3-Pad3)") (class "Default")
      (node (ref "U1") (pin "3") (pinfunction "IO_L01N_3_3") (pintype "bidirectional+no_connect"))
    )
    (net (code "67") (name "unconnected-(U1D-IO_L01P_3-Pad2)") (class "Default")
      (node (ref "U1") (pin "2") (pinfunction "IO_L01P_3_2") (pintype "bidirectional+no_connect"))
    )
    (net (code "68") (name "unconnected-(U1D-IO_L02N_3{slash}VREF_3-Pad5)") (class "Default")
      (node (ref "U1") (pin "5") (pinfunction "IO_L02N_3/VREF_3_5") (pintype "bidirectional+no_connect"))
    )
    (net (code "69") (name "unconnected-(U1D-IO_L02P_3-Pad4)") (class "Default")
      (node (ref "U1") (pin "4") (pinfunction "IO_L02P_3_4") (pintype "bidirectional+no_connect"))
    )
    (net (code "70") (name "unconnected-(U1D-IO_L03N_3-Pad9)") (class "Default")
      (node (ref "U1") (pin "9") (pinfunction "IO_L03N_3_9") (pintype "bidirectional+no_connect"))
    )
    (net (code "71") (name "unconnected-(U1D-IO_L03P_3-Pad8)") (class "Default")
      (node (ref "U1") (pin "8") (pinfunction "IO_L03P_3_8") (pintype "bidirectional+no_connect"))
    )
    (net (code "72") (name "unconnected-(U1D-IO_L04N_3-Pad12)") (class "Default")
      (node (ref "U1") (pin "12") (pinfunction "IO_L04N_3_12") (pintype "bidirectional+no_connect"))
    )
    (net (code "73") (name "unconnected-(U1D-IO_L04P_3-Pad11)") (class "Default")
      (node (ref "U1") (pin "11") (pinfunction "IO_L04P_3_11") (pintype "bidirectional+no_connect"))
    )
    (net (code "74") (name "unconnected-(U1D-IO_L05N_3-Pad16)") (class "Default")
      (node (ref "U1") (pin "16") (pinfunction "IO_L05N_3_16") (pintype "bidirectional+no_connect"))
    )
    (net (code "75") (name "unconnected-(U1D-IO_L06N_3-Pad19)") (class "Default")
      (node (ref "U1") (pin "19") (pinfunction "IO_L06N_3_19") (pintype "bidirectional+no_connect"))
    )
    (net (code "76") (name "unconnected-(U1D-IO_L08N_3{slash}LHCLK3-Pad25)") (class "Default")
      (node (ref "U1") (pin "25") (pinfunction "IO_L08N_3/LHCLK3_25") (pintype "bidirectional+no_connect"))
    )
    (net (code "77") (name "unconnected-(U1D-IO_L09N_3{slash}LHCLK5-Pad29)") (class "Default")
      (node (ref "U1") (pin "29") (pinfunction "IO_L09N_3/LHCLK5_29") (pintype "bidirectional+no_connect"))
    )
    (net (code "78") (name "unconnected-(U1D-IO_L10N_3{slash}LHCLK7-Pad31)") (class "Default")
      (node (ref "U1") (pin "31") (pinfunction "IO_L10N_3/LHCLK7_31") (pintype "bidirectional+no_connect"))
    )
    (net (code "79") (name "unconnected-(U1D-IO_L11P_3-Pad33)") (class "Default")
      (node (ref "U1") (pin "33") (pinfunction "IO_L11P_3_33") (pintype "bidirectional+no_connect"))
    )
    (net (code "80") (name "unconnected-(U1D-IO_L12N_3-Pad36)") (class "Default")
      (node (ref "U1") (pin "36") (pinfunction "IO_L12N_3_36") (pintype "bidirectional+no_connect"))
    )
    (net (code "81") (name "unconnected-(U1D-IO_L12P_3-Pad35)") (class "Default")
      (node (ref "U1") (pin "35") (pinfunction "IO_L12P_3_35") (pintype "bidirectional+no_connect"))
    )
    (net (code "82") (name "unconnected-(U1D-IO_L13N_3-Pad40)") (class "Default")
      (node (ref "U1") (pin "40") (pinfunction "IO_L13N_3_40") (pintype "bidirectional+no_connect"))
    )
    (net (code "83") (name "unconnected-(U1D-IO_L13P_3-Pad39)") (class "Default")
      (node (ref "U1") (pin "39") (pinfunction "IO_L13P_3_39") (pintype "bidirectional+no_connect"))
    )
    (net (code "84") (name "unconnected-(U1D-IO_L14N_3-Pad42)") (class "Default")
      (node (ref "U1") (pin "42") (pinfunction "IO_L14N_3_42") (pintype "bidirectional+no_connect"))
    )
    (net (code "85") (name "unconnected-(U1D-IO_L14P_3-Pad41)") (class "Default")
      (node (ref "U1") (pin "41") (pinfunction "IO_L14P_3_41") (pintype "bidirectional+no_connect"))
    )
    (net (code "86") (name "unconnected-(U1D-IO_L15N_3-Pad48)") (class "Default")
      (node (ref "U1") (pin "48") (pinfunction "IO_L15N_3_48") (pintype "bidirectional+no_connect"))
    )
    (net (code "87") (name "unconnected-(U1D-IO_L15P_3-Pad47)") (class "Default")
      (node (ref "U1") (pin "47") (pinfunction "IO_L15P_3_47") (pintype "bidirectional+no_connect"))
    )
    (net (code "88") (name "unconnected-(U1D-IO_L16N_3-Pad50)") (class "Default")
      (node (ref "U1") (pin "50") (pinfunction "IO_L16N_3_50") (pintype "bidirectional+no_connect"))
    )
    (net (code "89") (name "unconnected-(U1D-IO_L16P_3-Pad49)") (class "Default")
      (node (ref "U1") (pin "49") (pinfunction "IO_L16P_3_49") (pintype "bidirectional+no_connect"))
    )
    (net (code "90") (name "unconnected-(U1D-IO{slash}VREF_3-Pad45)") (class "Default")
      (node (ref "U1") (pin "45") (pinfunction "IO/VREF_3_45") (pintype "bidirectional+no_connect"))
    )
    (net (code "91") (name "unconnected-(U9-SYNC_IN-Pad1)") (class "Default")
      (node (ref "U9") (pin "1") (pinfunction "SYNC_IN_1") (pintype "input+no_connect"))
    )
    (net (code "92") (name "unconnected-(U9-SYNC_OUT-Pad2)") (class "Default")
      (node (ref "U9") (pin "2") (pinfunction "SYNC_OUT_2") (pintype "output+no_connect"))
    )
    (net (code "93") (name "unconnected-(U10-NC-Pad5)") (class "Default")
      (node (ref "U10") (pin "5") (pinfunction "NC_5") (pintype "passive+no_connect"))
    )
    (net (code "94") (name "unconnected-(U11-NC-Pad5)") (class "Default")
      (node (ref "U11") (pin "5") (pinfunction "NC_5") (pintype "passive+no_connect"))
    )
  )
)
